# 10_RF_2.net
KiCad netlist of a schematic drawn in Altium Designer
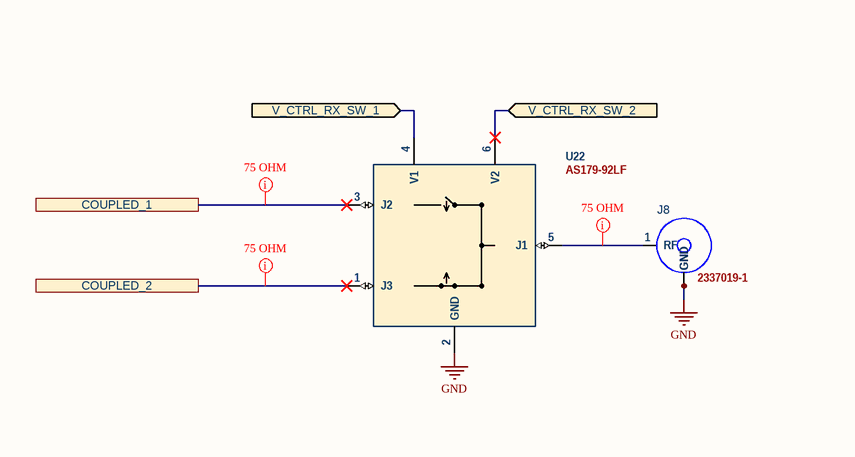
[diagram p0: 10_RF_2.SchDoc, left]
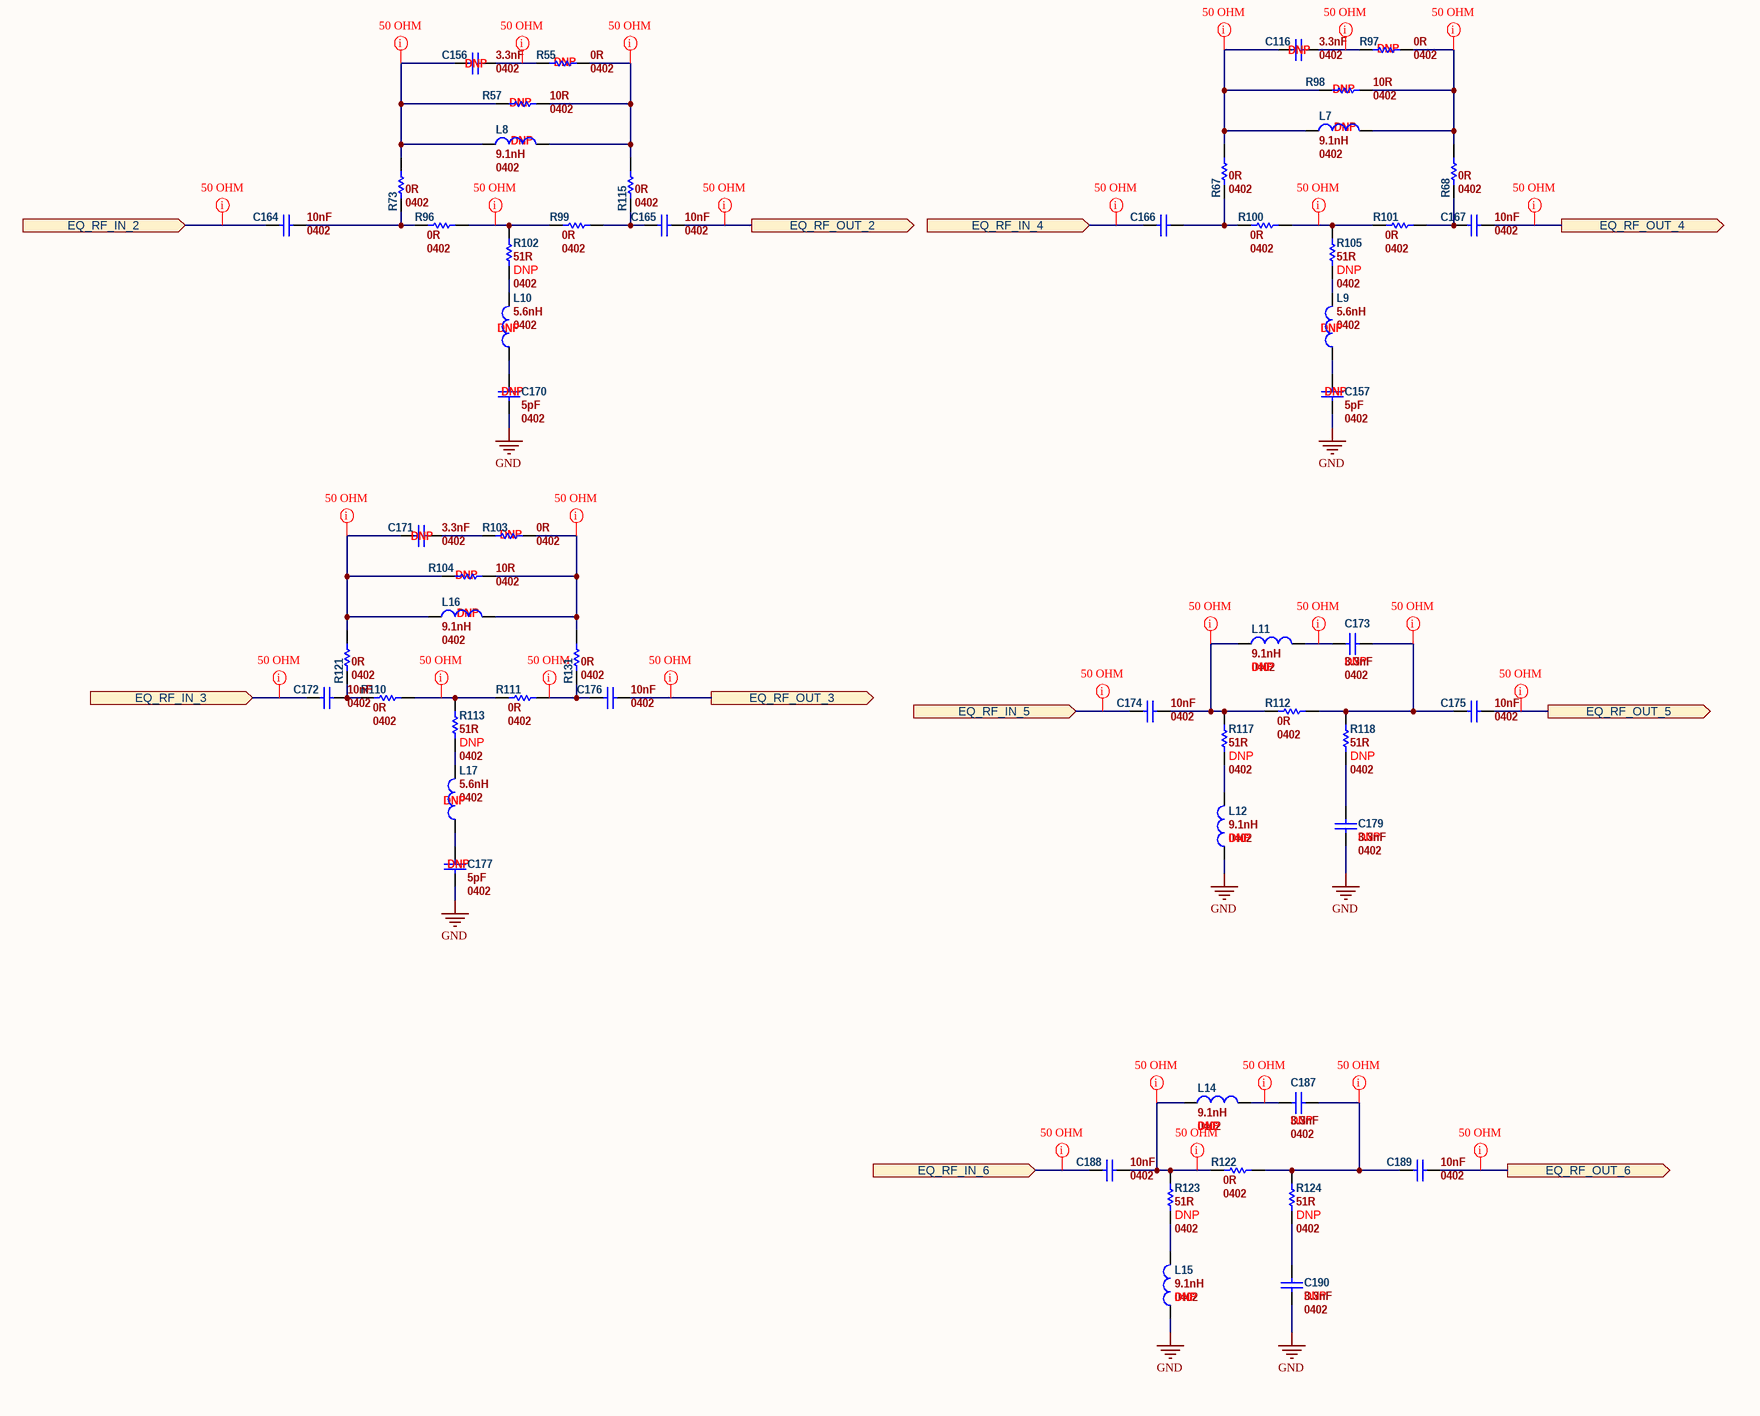
[diagram p1: 10_RF_2.SchDoc, right]

(export (version "E")
  (design (tool "Eeschema 10.0.6"))
  (components
    (comp (ref "C116")
      (value "3.3nF")
      (footprint "DISCRETE:CAP_0402_N")
      (description "CAP CER 3.3nF 50V X7R 0402 ±5%")
      (fields
        (field (name "TOLERANCE") "±5%")
        (field (name "ASSEMBLY") "DNP")
        (field (name "PACKAGE") "0402")
        (field (name "Comment") "C 0402 50V X7R - 3.3nF")
      )
      (libsource (lib "CAPACITOR") (part "C 0402 50V X7R - 3.3nF"))
    )
    (comp (ref "C156")
      (value "3.3nF")
      (footprint "DISCRETE:CAP_0402_N")
      (description "CAP CER 3.3nF 50V X7R 0402 ±5%")
      (fields
        (field (name "TOLERANCE") "±5%")
        (field (name "ASSEMBLY") "DNP")
        (field (name "PACKAGE") "0402")
        (field (name "Comment") "C 0402 50V X7R - 3.3nF")
      )
      (libsource (lib "CAPACITOR") (part "C 0402 50V X7R - 3.3nF"))
    )
    (comp (ref "C157")
      (value "5pF")
      (footprint "DISCRETE:CAP_0402_N")
      (description "CAP CER 5pF 50V C0G/NP0 0402 ±0.1pF")
      (fields
        (field (name "TOLERANCE") "±0.1pF")
        (field (name "ASSEMBLY") "DNP")
        (field (name "PACKAGE") "0402")
        (field (name "Comment") "C 0402 50V C0G/NP0 - 5pF")
      )
      (libsource (lib "CAPACITOR") (part "C 0402 50V C0G/NP0 - 5pF"))
    )
    (comp (ref "C164")
      (value "10nF")
      (footprint "DISCRETE:CAP_0402_N")
      (description "CAP CER 10nF 50V X7R 0402 ±10%")
      (fields
        (field (name "TOLERANCE") "±10%")
        (field (name "PACKAGE") "0402")
        (field (name "Comment") "C 0402 50V X7R - 10nF")
      )
      (libsource (lib "CAPACITOR") (part "C 0402 50V X7R - 10nF"))
    )
    (comp (ref "C165")
      (value "10nF")
      (footprint "DISCRETE:CAP_0402_N")
      (description "CAP CER 10nF 50V X7R 0402 ±10%")
      (fields
        (field (name "TOLERANCE") "±10%")
        (field (name "PACKAGE") "0402")
        (field (name "Comment") "C 0402 50V X7R - 10nF")
      )
      (libsource (lib "CAPACITOR") (part "C 0402 50V X7R - 10nF"))
    )
    (comp (ref "C166")
      (value "C 0402 50V X7R - 10nF")
      (footprint "DISCRETE:CAP_0402_N")
      (description "CAP CER 10nF 50V X7R 0402 ±10%")
      (fields (field (name "TOLERANCE") "±10%"))
      (libsource (lib "CAPACITOR") (part "C 0402 50V X7R - 10nF"))
    )
    (comp (ref "C167")
      (value "10nF")
      (footprint "DISCRETE:CAP_0402_N")
      (description "CAP CER 10nF 50V X7R 0402 ±10%")
      (fields
        (field (name "TOLERANCE") "±10%")
        (field (name "PACKAGE") "0402")
        (field (name "Comment") "C 0402 50V X7R - 10nF")
      )
      (libsource (lib "CAPACITOR") (part "C 0402 50V X7R - 10nF"))
    )
    (comp (ref "C170")
      (value "5pF")
      (footprint "DISCRETE:CAP_0402_N")
      (description "CAP CER 5pF 50V C0G/NP0 0402 ±0.1pF")
      (fields
        (field (name "TOLERANCE") "±0.1pF")
        (field (name "ASSEMBLY") "DNP")
        (field (name "PACKAGE") "0402")
        (field (name "Comment") "C 0402 50V C0G/NP0 - 5pF")
      )
      (libsource (lib "CAPACITOR") (part "C 0402 50V C0G/NP0 - 5pF"))
    )
    (comp (ref "C171")
      (value "3.3nF")
      (footprint "DISCRETE:CAP_0402_N")
      (description "CAP CER 3.3nF 50V X7R 0402 ±5%")
      (fields
        (field (name "TOLERANCE") "±5%")
        (field (name "ASSEMBLY") "DNP")
        (field (name "PACKAGE") "0402")
        (field (name "Comment") "C 0402 50V X7R - 3.3nF")
      )
      (libsource (lib "CAPACITOR") (part "C 0402 50V X7R - 3.3nF"))
    )
    (comp (ref "C172")
      (value "10nF")
      (footprint "DISCRETE:CAP_0402_N")
      (description "CAP CER 10nF 50V X7R 0402 ±10%")
      (fields
        (field (name "TOLERANCE") "±10%")
        (field (name "PACKAGE") "0402")
        (field (name "Comment") "C 0402 50V X7R - 10nF")
      )
      (libsource (lib "CAPACITOR") (part "C 0402 50V X7R - 10nF"))
    )
    (comp (ref "C173")
      (value "3.3nF")
      (footprint "DISCRETE:CAP_0402_N")
      (description "CAP CER 3.3nF 50V X7R 0402 ±5%")
      (fields
        (field (name "TOLERANCE") "±5%")
        (field (name "ASSEMBLY") "DNP")
        (field (name "PACKAGE") "0402")
        (field (name "Comment") "C 0402 50V X7R - 3.3nF")
      )
      (libsource (lib "CAPACITOR") (part "C 0402 50V X7R - 3.3nF"))
    )
    (comp (ref "C174")
      (value "10nF")
      (footprint "DISCRETE:CAP_0402_N")
      (description "CAP CER 10nF 50V X7R 0402 ±10%")
      (fields
        (field (name "TOLERANCE") "±10%")
        (field (name "PACKAGE") "0402")
        (field (name "Comment") "C 0402 50V X7R - 10nF")
      )
      (libsource (lib "CAPACITOR") (part "C 0402 50V X7R - 10nF"))
    )
    (comp (ref "C175")
      (value "10nF")
      (footprint "DISCRETE:CAP_0402_N")
      (description "CAP CER 10nF 50V X7R 0402 ±10%")
      (fields
        (field (name "TOLERANCE") "±10%")
        (field (name "PACKAGE") "0402")
        (field (name "Comment") "C 0402 50V X7R - 10nF")
      )
      (libsource (lib "CAPACITOR") (part "C 0402 50V X7R - 10nF"))
    )
    (comp (ref "C176")
      (value "10nF")
      (footprint "DISCRETE:CAP_0402_N")
      (description "CAP CER 10nF 50V X7R 0402 ±10%")
      (fields
        (field (name "TOLERANCE") "±10%")
        (field (name "PACKAGE") "0402")
        (field (name "Comment") "C 0402 50V X7R - 10nF")
      )
      (libsource (lib "CAPACITOR") (part "C 0402 50V X7R - 10nF"))
    )
    (comp (ref "C177")
      (value "5pF")
      (footprint "DISCRETE:CAP_0402_N")
      (description "CAP CER 5pF 50V C0G/NP0 0402 ±0.1pF")
      (fields
        (field (name "TOLERANCE") "±0.1pF")
        (field (name "ASSEMBLY") "DNP")
        (field (name "PACKAGE") "0402")
        (field (name "Comment") "C 0402 50V C0G/NP0 - 5pF")
      )
      (libsource (lib "CAPACITOR") (part "C 0402 50V C0G/NP0 - 5pF"))
    )
    (comp (ref "C179")
      (value "3.3nF")
      (footprint "DISCRETE:CAP_0402_N")
      (description "CAP CER 3.3nF 50V X7R 0402 ±5%")
      (fields
        (field (name "TOLERANCE") "±5%")
        (field (name "ASSEMBLY") "DNP")
        (field (name "PACKAGE") "0402")
        (field (name "Comment") "C 0402 50V X7R - 3.3nF")
      )
      (libsource (lib "CAPACITOR") (part "C 0402 50V X7R - 3.3nF"))
    )
    (comp (ref "C187")
      (value "3.3nF")
      (footprint "DISCRETE:CAP_0402_N")
      (description "CAP CER 3.3nF 50V X7R 0402 ±5%")
      (fields
        (field (name "TOLERANCE") "±5%")
        (field (name "ASSEMBLY") "DNP")
        (field (name "PACKAGE") "0402")
        (field (name "Comment") "C 0402 50V X7R - 3.3nF")
      )
      (libsource (lib "CAPACITOR") (part "C 0402 50V X7R - 3.3nF"))
    )
    (comp (ref "C188")
      (value "10nF")
      (footprint "DISCRETE:CAP_0402_N")
      (description "CAP CER 10nF 50V X7R 0402 ±10%")
      (fields
        (field (name "TOLERANCE") "±10%")
        (field (name "PACKAGE") "0402")
        (field (name "Comment") "C 0402 50V X7R - 10nF")
      )
      (libsource (lib "CAPACITOR") (part "C 0402 50V X7R - 10nF"))
    )
    (comp (ref "C189")
      (value "10nF")
      (footprint "DISCRETE:CAP_0402_N")
      (description "CAP CER 10nF 50V X7R 0402 ±10%")
      (fields
        (field (name "TOLERANCE") "±10%")
        (field (name "PACKAGE") "0402")
        (field (name "Comment") "C 0402 50V X7R - 10nF")
      )
      (libsource (lib "CAPACITOR") (part "C 0402 50V X7R - 10nF"))
    )
    (comp (ref "C190")
      (value "3.3nF")
      (footprint "DISCRETE:CAP_0402_N")
      (description "CAP CER 3.3nF 50V X7R 0402 ±5%")
      (fields
        (field (name "TOLERANCE") "±5%")
        (field (name "ASSEMBLY") "DNP")
        (field (name "PACKAGE") "0402")
        (field (name "Comment") "C 0402 50V X7R - 3.3nF")
      )
      (libsource (lib "CAPACITOR") (part "C 0402 50V X7R - 3.3nF"))
    )
    (comp (ref "J8")
      (value "2337019-1")
      (footprint "2337019-1")
      (description "CONN UMCC(UFL) COAX MALE 50 OHM SMD -40°C~85°C")
      (libsource (lib "SMARTCATV") (part "2337019-1"))
    )
    (comp (ref "L7")
      (value "9.1nH")
      (footprint "DISCRETE:IND_0402_N")
      (description "IND 9.1nH 500mA 270mΩ DCR 0402 ±5% -55°C~125°C")
      (fields
        (field (name "TOLERANCE") "±5%")
        (field (name "PACKAGE") "0402")
        (field (name "ASSEMBLY") "DNP")
        (field (name "Comment") "L 0402 500mA - 9.1nH")
        (field (name "COMPONENTLINK2URL") "D:\\SAVRONIK_SVN\\Donanım\\trunk\\ALTIUM\\Central Library\\Datasheets\\Inductor\\LQG15HN9N1J02D_Datasheet.pdf")
      )
      (libsource (lib "INDUCTOR") (part "L 0402 500mA - 9.1nH"))
    )
    (comp (ref "L8")
      (value "9.1nH")
      (footprint "DISCRETE:IND_0402_N")
      (description "IND 9.1nH 500mA 270mΩ DCR 0402 ±5% -55°C~125°C")
      (fields
        (field (name "TOLERANCE") "±5%")
        (field (name "PACKAGE") "0402")
        (field (name "ASSEMBLY") "DNP")
        (field (name "Comment") "L 0402 500mA - 9.1nH")
        (field (name "COMPONENTLINK2URL") "D:\\SAVRONIK_SVN\\Donanım\\trunk\\ALTIUM\\Central Library\\Datasheets\\Inductor\\LQG15HN9N1J02D_Datasheet.pdf")
      )
      (libsource (lib "INDUCTOR") (part "L 0402 500mA - 9.1nH"))
    )
    (comp (ref "L9")
      (value "5.6nH")
      (footprint "DISCRETE:IND_0402_N")
      (description "IND 5.6nH 650mA 200mΩ DCR 0402 ±0.3nH -55°C~125°C")
      (fields
        (field (name "TOLERANCE") "±0.3nH")
        (field (name "PACKAGE") "0402")
        (field (name "ASSEMBLY") "DNP")
        (field (name "Comment") "L 0402 650mA - 5.6nH")
        (field (name "COMPONENTLINK2URL") "D:\\SAVRONIK_SVN\\Donanım\\trunk\\ALTIUM\\Central Library\\Datasheets\\Inductor\\LQG15HS5N6S02D_Datasheet.pdf")
      )
      (libsource (lib "INDUCTOR") (part "L 0402 650mA - 5.6nH"))
    )
    (comp (ref "L10")
      (value "5.6nH")
      (footprint "DISCRETE:IND_0402_N")
      (description "IND 5.6nH 650mA 200mΩ DCR 0402 ±0.3nH -55°C~125°C")
      (fields
        (field (name "TOLERANCE") "±0.3nH")
        (field (name "PACKAGE") "0402")
        (field (name "ASSEMBLY") "DNP")
        (field (name "Comment") "L 0402 650mA - 5.6nH")
        (field (name "COMPONENTLINK2URL") "D:\\SAVRONIK_SVN\\Donanım\\trunk\\ALTIUM\\Central Library\\Datasheets\\Inductor\\LQG15HS5N6S02D_Datasheet.pdf")
      )
      (libsource (lib "INDUCTOR") (part "L 0402 650mA - 5.6nH"))
    )
    (comp (ref "L11")
      (value "9.1nH")
      (footprint "DISCRETE:IND_0402_N")
      (description "IND 9.1nH 500mA 270mΩ DCR 0402 ±5% -55°C~125°C")
      (fields
        (field (name "TOLERANCE") "±5%")
        (field (name "PACKAGE") "0402")
        (field (name "ASSEMBLY") "DNP")
        (field (name "Comment") "L 0402 500mA - 9.1nH")
        (field (name "COMPONENTLINK2URL") "D:\\SAVRONIK_SVN\\Donanım\\trunk\\ALTIUM\\Central Library\\Datasheets\\Inductor\\LQG15HN9N1J02D_Datasheet.pdf")
      )
      (libsource (lib "INDUCTOR") (part "L 0402 500mA - 9.1nH"))
    )
    (comp (ref "L12")
      (value "9.1nH")
      (footprint "DISCRETE:IND_0402_N")
      (description "IND 9.1nH 500mA 270mΩ DCR 0402 ±5% -55°C~125°C")
      (fields
        (field (name "TOLERANCE") "±5%")
        (field (name "PACKAGE") "0402")
        (field (name "ASSEMBLY") "DNP")
        (field (name "Comment") "L 0402 500mA - 9.1nH")
        (field (name "COMPONENTLINK2URL") "D:\\SAVRONIK_SVN\\Donanım\\trunk\\ALTIUM\\Central Library\\Datasheets\\Inductor\\LQG15HN9N1J02D_Datasheet.pdf")
      )
      (libsource (lib "INDUCTOR") (part "L 0402 500mA - 9.1nH"))
    )
    (comp (ref "L14")
      (value "9.1nH")
      (footprint "DISCRETE:IND_0402_N")
      (description "IND 9.1nH 500mA 270mΩ DCR 0402 ±5% -55°C~125°C")
      (fields
        (field (name "TOLERANCE") "±5%")
        (field (name "PACKAGE") "0402")
        (field (name "ASSEMBLY") "DNP")
        (field (name "Comment") "L 0402 500mA - 9.1nH")
        (field (name "COMPONENTLINK2URL") "D:\\SAVRONIK_SVN\\Donanım\\trunk\\ALTIUM\\Central Library\\Datasheets\\Inductor\\LQG15HN9N1J02D_Datasheet.pdf")
      )
      (libsource (lib "INDUCTOR") (part "L 0402 500mA - 9.1nH"))
    )
    (comp (ref "L15")
      (value "9.1nH")
      (footprint "DISCRETE:IND_0402_N")
      (description "IND 9.1nH 500mA 270mΩ DCR 0402 ±5% -55°C~125°C")
      (fields
        (field (name "TOLERANCE") "±5%")
        (field (name "PACKAGE") "0402")
        (field (name "ASSEMBLY") "DNP")
        (field (name "Comment") "L 0402 500mA - 9.1nH")
        (field (name "COMPONENTLINK2URL") "D:\\SAVRONIK_SVN\\Donanım\\trunk\\ALTIUM\\Central Library\\Datasheets\\Inductor\\LQG15HN9N1J02D_Datasheet.pdf")
      )
      (libsource (lib "INDUCTOR") (part "L 0402 500mA - 9.1nH"))
    )
    (comp (ref "L16")
      (value "9.1nH")
      (footprint "DISCRETE:IND_0402_N")
      (description "IND 9.1nH 500mA 270mΩ DCR 0402 ±5% -55°C~125°C")
      (fields
        (field (name "TOLERANCE") "±5%")
        (field (name "PACKAGE") "0402")
        (field (name "ASSEMBLY") "DNP")
        (field (name "Comment") "L 0402 500mA - 9.1nH")
        (field (name "COMPONENTLINK2URL") "D:\\SAVRONIK_SVN\\Donanım\\trunk\\ALTIUM\\Central Library\\Datasheets\\Inductor\\LQG15HN9N1J02D_Datasheet.pdf")
      )
      (libsource (lib "INDUCTOR") (part "L 0402 500mA - 9.1nH"))
    )
    (comp (ref "L17")
      (value "5.6nH")
      (footprint "DISCRETE:IND_0402_N")
      (description "IND 5.6nH 650mA 200mΩ DCR 0402 ±0.3nH -55°C~125°C")
      (fields
        (field (name "TOLERANCE") "±0.3nH")
        (field (name "PACKAGE") "0402")
        (field (name "ASSEMBLY") "DNP")
        (field (name "Comment") "L 0402 650mA - 5.6nH")
        (field (name "COMPONENTLINK2URL") "D:\\SAVRONIK_SVN\\Donanım\\trunk\\ALTIUM\\Central Library\\Datasheets\\Inductor\\LQG15HS5N6S02D_Datasheet.pdf")
      )
      (libsource (lib "INDUCTOR") (part "L 0402 650mA - 5.6nH"))
    )
    (comp (ref "R55")
      (value "0R")
      (footprint "DISCRETE:RES_0402_N")
      (description "RES 0R 1/10W 0402")
      (fields
        (field (name "ASSEMBLY") "DNP")
        (field (name "PACKAGE") "0402")
        (field (name "Comment") "R 0402 1/10W - 0R")
      )
      (libsource (lib "RESISTOR") (part "R 0402 1/10W - 0R"))
    )
    (comp (ref "R57")
      (value "10R")
      (footprint "DISCRETE:RES_0402_N")
      (description "RES 10R 1/10W 0402 1%")
      (fields
        (field (name "TOLERANCE") "±1%")
        (field (name "ASSEMBLY") "DNP")
        (field (name "PACKAGE") "0402")
        (field (name "Comment") "R 0402 1/10W 1% - 10R")
      )
      (libsource (lib "RESISTOR") (part "R 0402 1/10W 1% - 10R"))
    )
    (comp (ref "R67")
      (value "0R")
      (footprint "DISCRETE:RES_0402_N")
      (description "RES 0R 1/10W 0402")
      (fields (field (name "PACKAGE") "0402") (field (name "Comment") "R 0402 1/10W - 0R"))
      (libsource (lib "RESISTOR") (part "R 0402 1/10W - 0R"))
    )
    (comp (ref "R68")
      (value "0R")
      (footprint "DISCRETE:RES_0402_N")
      (description "RES 0R 1/10W 0402")
      (fields (field (name "PACKAGE") "0402") (field (name "Comment") "R 0402 1/10W - 0R"))
      (libsource (lib "RESISTOR") (part "R 0402 1/10W - 0R"))
    )
    (comp (ref "R73")
      (value "0R")
      (footprint "DISCRETE:RES_0402_N")
      (description "RES 0R 1/10W 0402")
      (fields (field (name "PACKAGE") "0402") (field (name "Comment") "R 0402 1/10W - 0R"))
      (libsource (lib "RESISTOR") (part "R 0402 1/10W - 0R"))
    )
    (comp (ref "R96")
      (value "0R")
      (footprint "DISCRETE:RES_0402_N")
      (description "RES 0R 1/10W 0402")
      (fields (field (name "PACKAGE") "0402") (field (name "Comment") "R 0402 1/10W - 0R"))
      (libsource (lib "RESISTOR") (part "R 0402 1/10W - 0R"))
    )
    (comp (ref "R97")
      (value "0R")
      (footprint "DISCRETE:RES_0402_N")
      (description "RES 0R 1/10W 0402")
      (fields
        (field (name "ASSEMBLY") "DNP")
        (field (name "PACKAGE") "0402")
        (field (name "Comment") "R 0402 1/10W - 0R")
      )
      (libsource (lib "RESISTOR") (part "R 0402 1/10W - 0R"))
    )
    (comp (ref "R98")
      (value "10R")
      (footprint "DISCRETE:RES_0402_N")
      (description "RES 10R 1/10W 0402 1%")
      (fields
        (field (name "TOLERANCE") "±1%")
        (field (name "ASSEMBLY") "DNP")
        (field (name "PACKAGE") "0402")
        (field (name "Comment") "R 0402 1/10W 1% - 10R")
      )
      (libsource (lib "RESISTOR") (part "R 0402 1/10W 1% - 10R"))
    )
    (comp (ref "R99")
      (value "0R")
      (footprint "DISCRETE:RES_0402_N")
      (description "RES 0R 1/10W 0402")
      (fields (field (name "PACKAGE") "0402") (field (name "Comment") "R 0402 1/10W - 0R"))
      (libsource (lib "RESISTOR") (part "R 0402 1/10W - 0R"))
    )
    (comp (ref "R100")
      (value "0R")
      (footprint "DISCRETE:RES_0402_N")
      (description "RES 0R 1/10W 0402")
      (fields (field (name "PACKAGE") "0402") (field (name "Comment") "R 0402 1/10W - 0R"))
      (libsource (lib "RESISTOR") (part "R 0402 1/10W - 0R"))
    )
    (comp (ref "R101")
      (value "0R")
      (footprint "DISCRETE:RES_0402_N")
      (description "RES 0R 1/10W 0402")
      (fields (field (name "PACKAGE") "0402") (field (name "Comment") "R 0402 1/10W - 0R"))
      (libsource (lib "RESISTOR") (part "R 0402 1/10W - 0R"))
    )
    (comp (ref "R102")
      (value "51R")
      (footprint "RES_0402_N")
      (description "RES 51R 1/10W 0402 1%")
      (fields
        (field (name "TOLERANCE") "±1%")
        (field (name "ASSEMBLY") "DNP")
        (field (name "PACKAGE") "0402")
        (field (name "Comment") "R 0402 1/10W 1% - 51R")
      )
      (libsource (lib "SMARTCATV") (part "R 0402 1/10W 1% - 51R"))
    )
    (comp (ref "R103")
      (value "0R")
      (footprint "DISCRETE:RES_0402_N")
      (description "RES 0R 1/10W 0402")
      (fields
        (field (name "ASSEMBLY") "DNP")
        (field (name "PACKAGE") "0402")
        (field (name "Comment") "R 0402 1/10W - 0R")
      )
      (libsource (lib "RESISTOR") (part "R 0402 1/10W - 0R"))
    )
    (comp (ref "R104")
      (value "10R")
      (footprint "DISCRETE:RES_0402_N")
      (description "RES 10R 1/10W 0402 1%")
      (fields
        (field (name "TOLERANCE") "±1%")
        (field (name "ASSEMBLY") "DNP")
        (field (name "PACKAGE") "0402")
        (field (name "Comment") "R 0402 1/10W 1% - 10R")
      )
      (libsource (lib "RESISTOR") (part "R 0402 1/10W 1% - 10R"))
    )
    (comp (ref "R105")
      (value "51R")
      (footprint "RES_0402_N")
      (description "RES 51R 1/10W 0402 1%")
      (fields
        (field (name "TOLERANCE") "±1%")
        (field (name "ASSEMBLY") "DNP")
        (field (name "PACKAGE") "0402")
        (field (name "Comment") "R 0402 1/10W 1% - 51R")
      )
      (libsource (lib "SMARTCATV") (part "R 0402 1/10W 1% - 51R"))
    )
    (comp (ref "R110")
      (value "0R")
      (footprint "DISCRETE:RES_0402_N")
      (description "RES 0R 1/10W 0402")
      (fields (field (name "PACKAGE") "0402") (field (name "Comment") "R 0402 1/10W - 0R"))
      (libsource (lib "RESISTOR") (part "R 0402 1/10W - 0R"))
    )
    (comp (ref "R111")
      (value "0R")
      (footprint "DISCRETE:RES_0402_N")
      (description "RES 0R 1/10W 0402")
      (fields (field (name "PACKAGE") "0402") (field (name "Comment") "R 0402 1/10W - 0R"))
      (libsource (lib "RESISTOR") (part "R 0402 1/10W - 0R"))
    )
    (comp (ref "R112")
      (value "0R")
      (footprint "DISCRETE:RES_0402_N")
      (description "RES 0R 1/10W 0402")
      (fields (field (name "PACKAGE") "0402") (field (name "Comment") "R 0402 1/10W - 0R"))
      (libsource (lib "RESISTOR") (part "R 0402 1/10W - 0R"))
    )
    (comp (ref "R113")
      (value "51R")
      (footprint "RES_0402_N")
      (description "RES 51R 1/10W 0402 1%")
      (fields
        (field (name "TOLERANCE") "±1%")
        (field (name "ASSEMBLY") "DNP")
        (field (name "PACKAGE") "0402")
        (field (name "Comment") "R 0402 1/10W 1% - 51R")
      )
      (libsource (lib "SMARTCATV") (part "R 0402 1/10W 1% - 51R"))
    )
    (comp (ref "R115")
      (value "0R")
      (footprint "DISCRETE:RES_0402_N")
      (description "RES 0R 1/10W 0402")
      (fields (field (name "PACKAGE") "0402") (field (name "Comment") "R 0402 1/10W - 0R"))
      (libsource (lib "RESISTOR") (part "R 0402 1/10W - 0R"))
    )
    (comp (ref "R117")
      (value "51R")
      (footprint "RES_0402_N")
      (description "RES 51R 1/10W 0402 1%")
      (fields
        (field (name "TOLERANCE") "±1%")
        (field (name "ASSEMBLY") "DNP")
        (field (name "PACKAGE") "0402")
        (field (name "Comment") "R 0402 1/10W 1% - 51R")
      )
      (libsource (lib "SMARTCATV") (part "R 0402 1/10W 1% - 51R"))
    )
    (comp (ref "R118")
      (value "51R")
      (footprint "RES_0402_N")
      (description "RES 51R 1/10W 0402 1%")
      (fields
        (field (name "TOLERANCE") "±1%")
        (field (name "ASSEMBLY") "DNP")
        (field (name "PACKAGE") "0402")
        (field (name "Comment") "R 0402 1/10W 1% - 51R")
      )
      (libsource (lib "SMARTCATV") (part "R 0402 1/10W 1% - 51R"))
    )
    (comp (ref "R121")
      (value "0R")
      (footprint "DISCRETE:RES_0402_N")
      (description "RES 0R 1/10W 0402")
      (fields (field (name "PACKAGE") "0402") (field (name "Comment") "R 0402 1/10W - 0R"))
      (libsource (lib "RESISTOR") (part "R 0402 1/10W - 0R"))
    )
    (comp (ref "R122")
      (value "0R")
      (footprint "DISCRETE:RES_0402_N")
      (description "RES 0R 1/10W 0402")
      (fields (field (name "PACKAGE") "0402") (field (name "Comment") "R 0402 1/10W - 0R"))
      (libsource (lib "RESISTOR") (part "R 0402 1/10W - 0R"))
    )
    (comp (ref "R123")
      (value "51R")
      (footprint "RES_0402_N")
      (description "RES 51R 1/10W 0402 1%")
      (fields
        (field (name "TOLERANCE") "±1%")
        (field (name "ASSEMBLY") "DNP")
        (field (name "PACKAGE") "0402")
        (field (name "Comment") "R 0402 1/10W 1% - 51R")
      )
      (libsource (lib "SMARTCATV") (part "R 0402 1/10W 1% - 51R"))
    )
    (comp (ref "R124")
      (value "51R")
      (footprint "RES_0402_N")
      (description "RES 51R 1/10W 0402 1%")
      (fields
        (field (name "TOLERANCE") "±1%")
        (field (name "ASSEMBLY") "DNP")
        (field (name "PACKAGE") "0402")
        (field (name "Comment") "R 0402 1/10W 1% - 51R")
      )
      (libsource (lib "SMARTCATV") (part "R 0402 1/10W 1% - 51R"))
    )
    (comp (ref "R131")
      (value "0R")
      (footprint "DISCRETE:RES_0402_N")
      (description "RES 0R 1/10W 0402")
      (fields (field (name "PACKAGE") "0402") (field (name "Comment") "R 0402 1/10W - 0R"))
      (libsource (lib "RESISTOR") (part "R 0402 1/10W - 0R"))
    )
    (comp (ref "U22")
      (value "AS179-92LF")
      (footprint "SC70_SOT-363")
      (description "IC RF SWITCH SP2T 0.02-4GHZ SC-70 -40°C~85°C")
      (libsource (lib "SMARTCATV") (part "AS179-92LF"))
    )
  )
  (nets
    (net (code "1") (name "/COUPLED_1") (class "Default")
      (node (ref "U22") (pin "3") (pinfunction "J2_3") (pintype "bidirectional+no_connect"))
    )
    (net (code "2") (name "/COUPLED_2") (class "Default")
      (node (ref "U22") (pin "1") (pinfunction "J3_1") (pintype "bidirectional+no_connect"))
    )
    (net (code "3") (name "/EQ_RF_IN_2") (class "Default")
      (node (ref "C164") (pin "1") (pinfunction "1_1") (pintype "passive"))
    )
    (net (code "4") (name "/EQ_RF_IN_3") (class "Default")
      (node (ref "C172") (pin "1") (pinfunction "1_1") (pintype "passive"))
    )
    (net (code "5") (name "/EQ_RF_IN_4") (class "Default")
      (node (ref "C166") (pin "1") (pinfunction "1_1") (pintype "passive"))
    )
    (net (code "6") (name "/EQ_RF_IN_5") (class "Default")
      (node (ref "C174") (pin "1") (pinfunction "1_1") (pintype "passive"))
    )
    (net (code "7") (name "/EQ_RF_IN_6") (class "Default")
      (node (ref "C188") (pin "1") (pinfunction "1_1") (pintype "passive"))
    )
    (net (code "8") (name "/EQ_RF_OUT_2") (class "Default")
      (node (ref "C165") (pin "2") (pinfunction "2_2") (pintype "passive"))
    )
    (net (code "9") (name "/EQ_RF_OUT_3") (class "Default")
      (node (ref "C176") (pin "2") (pinfunction "2_2") (pintype "passive"))
    )
    (net (code "10") (name "/EQ_RF_OUT_4") (class "Default")
      (node (ref "C167") (pin "2") (pinfunction "2_2") (pintype "passive"))
    )
    (net (code "11") (name "/EQ_RF_OUT_5") (class "Default")
      (node (ref "C175") (pin "2") (pinfunction "2_2") (pintype "passive"))
    )
    (net (code "12") (name "/EQ_RF_OUT_6") (class "Default")
      (node (ref "C189") (pin "2") (pinfunction "2_2") (pintype "passive"))
    )
    (net (code "13") (name "/V_CTRL_RX_SW_1") (class "Default")
      (node (ref "U22") (pin "4") (pinfunction "V1_4") (pintype "passive"))
    )
    (net (code "14") (name "/V_CTRL_RX_SW_2") (class "Default")
      (node (ref "U22") (pin "6") (pinfunction "V2_6") (pintype "power_in+no_connect"))
    )
    (net (code "15") (name "GND") (class "Default")
      (node (ref "C157") (pin "1") (pinfunction "1_1") (pintype "passive"))
      (node (ref "C170") (pin "1") (pinfunction "1_1") (pintype "passive"))
      (node (ref "C177") (pin "1") (pinfunction "1_1") (pintype "passive"))
      (node (ref "C179") (pin "1") (pinfunction "1_1") (pintype "passive"))
      (node (ref "C190") (pin "1") (pinfunction "1_1") (pintype "passive"))
      (node (ref "J8") (pin "G1") (pinfunction "GND_G1") (pintype "passive"))
      (node (ref "J8") (pin "G2") (pinfunction "GND_G2") (pintype "passive"))
      (node (ref "L12") (pin "1") (pinfunction "1_1") (pintype "passive"))
      (node (ref "L15") (pin "1") (pinfunction "1_1") (pintype "passive"))
      (node (ref "U22") (pin "2") (pinfunction "GND_2") (pintype "passive"))
    )
    (net (code "16") (name "Net-(C116-Pad1)") (class "Default")
      (node (ref "C116") (pin "1") (pinfunction "1_1") (pintype "passive"))
      (node (ref "L7") (pin "1") (pinfunction "1_1") (pintype "passive"))
      (node (ref "R67") (pin "2") (pinfunction "2_2") (pintype "passive"))
      (node (ref "R98") (pin "1") (pinfunction "1_1") (pintype "passive"))
    )
    (net (code "17") (name "Net-(C116-Pad2)") (class "Default")
      (node (ref "C116") (pin "2") (pinfunction "2_2") (pintype "passive"))
      (node (ref "R97") (pin "1") (pinfunction "1_1") (pintype "passive"))
    )
    (net (code "18") (name "Net-(C156-Pad1)") (class "Default")
      (node (ref "C156") (pin "1") (pinfunction "1_1") (pintype "passive"))
      (node (ref "L8") (pin "1") (pinfunction "1_1") (pintype "passive"))
      (node (ref "R57") (pin "1") (pinfunction "1_1") (pintype "passive"))
      (node (ref "R73") (pin "2") (pinfunction "2_2") (pintype "passive"))
    )
    (net (code "19") (name "Net-(C156-Pad2)") (class "Default")
      (node (ref "C156") (pin "2") (pinfunction "2_2") (pintype "passive"))
      (node (ref "R55") (pin "1") (pinfunction "1_1") (pintype "passive"))
    )
    (net (code "20") (name "Net-(C157-Pad2)") (class "Default")
      (node (ref "C157") (pin "2") (pinfunction "2_2") (pintype "passive"))
      (node (ref "L9") (pin "1") (pinfunction "1_1") (pintype "passive"))
    )
    (net (code "21") (name "Net-(C164-Pad2)") (class "Default")
      (node (ref "C164") (pin "2") (pinfunction "2_2") (pintype "passive"))
      (node (ref "R73") (pin "1") (pinfunction "1_1") (pintype "passive"))
      (node (ref "R96") (pin "1") (pinfunction "1_1") (pintype "passive"))
    )
    (net (code "22") (name "Net-(C165-Pad1)") (class "Default")
      (node (ref "C165") (pin "1") (pinfunction "1_1") (pintype "passive"))
      (node (ref "R115") (pin "1") (pinfunction "1_1") (pintype "passive"))
      (node (ref "R99") (pin "2") (pinfunction "2_2") (pintype "passive"))
    )
    (net (code "23") (name "Net-(C166-Pad2)") (class "Default")
      (node (ref "C166") (pin "2") (pinfunction "2_2") (pintype "passive"))
      (node (ref "R100") (pin "1") (pinfunction "1_1") (pintype "passive"))
      (node (ref "R67") (pin "1") (pinfunction "1_1") (pintype "passive"))
    )
    (net (code "24") (name "Net-(C167-Pad1)") (class "Default")
      (node (ref "C167") (pin "1") (pinfunction "1_1") (pintype "passive"))
      (node (ref "R101") (pin "2") (pinfunction "2_2") (pintype "passive"))
      (node (ref "R68") (pin "1") (pinfunction "1_1") (pintype "passive"))
    )
    (net (code "25") (name "Net-(C170-Pad2)") (class "Default")
      (node (ref "C170") (pin "2") (pinfunction "2_2") (pintype "passive"))
      (node (ref "L10") (pin "1") (pinfunction "1_1") (pintype "passive"))
    )
    (net (code "26") (name "Net-(C171-Pad1)") (class "Default")
      (node (ref "C171") (pin "1") (pinfunction "1_1") (pintype "passive"))
      (node (ref "L16") (pin "1") (pinfunction "1_1") (pintype "passive"))
      (node (ref "R104") (pin "1") (pinfunction "1_1") (pintype "passive"))
      (node (ref "R121") (pin "2") (pinfunction "2_2") (pintype "passive"))
    )
    (net (code "27") (name "Net-(C171-Pad2)") (class "Default")
      (node (ref "C171") (pin "2") (pinfunction "2_2") (pintype "passive"))
      (node (ref "R103") (pin "1") (pinfunction "1_1") (pintype "passive"))
    )
    (net (code "28") (name "Net-(C172-Pad2)") (class "Default")
      (node (ref "C172") (pin "2") (pinfunction "2_2") (pintype "passive"))
      (node (ref "R110") (pin "1") (pinfunction "1_1") (pintype "passive"))
      (node (ref "R121") (pin "1") (pinfunction "1_1") (pintype "passive"))
    )
    (net (code "29") (name "Net-(C173-Pad1)") (class "Default")
      (node (ref "C173") (pin "1") (pinfunction "1_1") (pintype "passive"))
      (node (ref "C175") (pin "1") (pinfunction "1_1") (pintype "passive"))
      (node (ref "R112") (pin "2") (pinfunction "2_2") (pintype "passive"))
      (node (ref "R118") (pin "2") (pinfunction "2_2") (pintype "passive"))
    )
    (net (code "30") (name "Net-(C173-Pad2)") (class "Default")
      (node (ref "C173") (pin "2") (pinfunction "2_2") (pintype "passive"))
      (node (ref "L11") (pin "2") (pinfunction "2_2") (pintype "passive"))
    )
    (net (code "31") (name "Net-(C174-Pad2)") (class "Default")
      (node (ref "C174") (pin "2") (pinfunction "2_2") (pintype "passive"))
      (node (ref "L11") (pin "1") (pinfunction "1_1") (pintype "passive"))
      (node (ref "R112") (pin "1") (pinfunction "1_1") (pintype "passive"))
      (node (ref "R117") (pin "2") (pinfunction "2_2") (pintype "passive"))
    )
    (net (code "32") (name "Net-(C176-Pad1)") (class "Default")
      (node (ref "C176") (pin "1") (pinfunction "1_1") (pintype "passive"))
      (node (ref "R111") (pin "2") (pinfunction "2_2") (pintype "passive"))
      (node (ref "R131") (pin "1") (pinfunction "1_1") (pintype "passive"))
    )
    (net (code "33") (name "Net-(C177-Pad2)") (class "Default")
      (node (ref "C177") (pin "2") (pinfunction "2_2") (pintype "passive"))
      (node (ref "L17") (pin "1") (pinfunction "1_1") (pintype "passive"))
    )
    (net (code "34") (name "Net-(C179-Pad2)") (class "Default")
      (node (ref "C179") (pin "2") (pinfunction "2_2") (pintype "passive"))
      (node (ref "R118") (pin "1") (pinfunction "1_1") (pintype "passive"))
    )
    (net (code "35") (name "Net-(C187-Pad1)") (class "Default")
      (node (ref "C187") (pin "1") (pinfunction "1_1") (pintype "passive"))
      (node (ref "C189") (pin "1") (pinfunction "1_1") (pintype "passive"))
      (node (ref "R122") (pin "2") (pinfunction "2_2") (pintype "passive"))
      (node (ref "R124") (pin "2") (pinfunction "2_2") (pintype "passive"))
    )
    (net (code "36") (name "Net-(C187-Pad2)") (class "Default")
      (node (ref "C187") (pin "2") (pinfunction "2_2") (pintype "passive"))
      (node (ref "L14") (pin "2") (pinfunction "2_2") (pintype "passive"))
    )
    (net (code "37") (name "Net-(C188-Pad2)") (class "Default")
      (node (ref "C188") (pin "2") (pinfunction "2_2") (pintype "passive"))
      (node (ref "L14") (pin "1") (pinfunction "1_1") (pintype "passive"))
      (node (ref "R122") (pin "1") (pinfunction "1_1") (pintype "passive"))
      (node (ref "R123") (pin "2") (pinfunction "2_2") (pintype "passive"))
    )
    (net (code "38") (name "Net-(C190-Pad2)") (class "Default")
      (node (ref "C190") (pin "2") (pinfunction "2_2") (pintype "passive"))
      (node (ref "R124") (pin "1") (pinfunction "1_1") (pintype "passive"))
    )
    (net (code "39") (name "Net-(J8-RF)") (class "Default")
      (node (ref "J8") (pin "1") (pinfunction "RF_1") (pintype "passive"))
      (node (ref "U22") (pin "5") (pinfunction "J1_5") (pintype "bidirectional"))
    )
    (net (code "40") (name "Net-(L7-Pad2)") (class "Default")
      (node (ref "L7") (pin "2") (pinfunction "2_2") (pintype "passive"))
      (node (ref "R68") (pin "2") (pinfunction "2_2") (pintype "passive"))
      (node (ref "R97") (pin "2") (pinfunction "2_2") (pintype "passive"))
      (node (ref "R98") (pin "2") (pinfunction "2_2") (pintype "passive"))
    )
    (net (code "41") (name "Net-(L8-Pad2)") (class "Default")
      (node (ref "L8") (pin "2") (pinfunction "2_2") (pintype "passive"))
      (node (ref "R115") (pin "2") (pinfunction "2_2") (pintype "passive"))
      (node (ref "R55") (pin "2") (pinfunction "2_2") (pintype "passive"))
      (node (ref "R57") (pin "2") (pinfunction "2_2") (pintype "passive"))
    )
    (net (code "42") (name "Net-(L9-Pad2)") (class "Default")
      (node (ref "L9") (pin "2") (pinfunction "2_2") (pintype "passive"))
      (node (ref "R105") (pin "1") (pinfunction "1_1") (pintype "passive"))
    )
    (net (code "43") (name "Net-(L10-Pad2)") (class "Default")
      (node (ref "L10") (pin "2") (pinfunction "2_2") (pintype "passive"))
      (node (ref "R102") (pin "1") (pinfunction "1_1") (pintype "passive"))
    )
    (net (code "44") (name "Net-(L12-Pad2)") (class "Default")
      (node (ref "L12") (pin "2") (pinfunction "2_2") (pintype "passive"))
      (node (ref "R117") (pin "1") (pinfunction "1_1") (pintype "passive"))
    )
    (net (code "45") (name "Net-(L15-Pad2)") (class "Default")
      (node (ref "L15") (pin "2") (pinfunction "2_2") (pintype "passive"))
      (node (ref "R123") (pin "1") (pinfunction "1_1") (pintype "passive"))
    )
    (net (code "46") (name "Net-(L16-Pad2)") (class "Default")
      (node (ref "L16") (pin "2") (pinfunction "2_2") (pintype "passive"))
      (node (ref "R103") (pin "2") (pinfunction "2_2") (pintype "passive"))
      (node (ref "R104") (pin "2") (pinfunction "2_2") (pintype "passive"))
      (node (ref "R131") (pin "2") (pinfunction "2_2") (pintype "passive"))
    )
    (net (code "47") (name "Net-(L17-Pad2)") (class "Default")
      (node (ref "L17") (pin "2") (pinfunction "2_2") (pintype "passive"))
      (node (ref "R113") (pin "1") (pinfunction "1_1") (pintype "passive"))
    )
    (net (code "48") (name "Net-(R100-Pad2)") (class "Default")
      (node (ref "R100") (pin "2") (pinfunction "2_2") (pintype "passive"))
      (node (ref "R101") (pin "1") (pinfunction "1_1") (pintype "passive"))
      (node (ref "R105") (pin "2") (pinfunction "2_2") (pintype "passive"))
    )
    (net (code "49") (name "Net-(R102-Pad2)") (class "Default")
      (node (ref "R102") (pin "2") (pinfunction "2_2") (pintype "passive"))
      (node (ref "R96") (pin "2") (pinfunction "2_2") (pintype "passive"))
      (node (ref "R99") (pin "1") (pinfunction "1_1") (pintype "passive"))
    )
    (net (code "50") (name "Net-(R110-Pad2)") (class "Default")
      (node (ref "R110") (pin "2") (pinfunction "2_2") (pintype "passive"))
      (node (ref "R111") (pin "1") (pinfunction "1_1") (pintype "passive"))
      (node (ref "R113") (pin "2") (pinfunction "2_2") (pintype "passive"))
    )
  )
)
